# LC_Meter_PTH.net
KiCad netlist of a schematic drawn in EAGLE
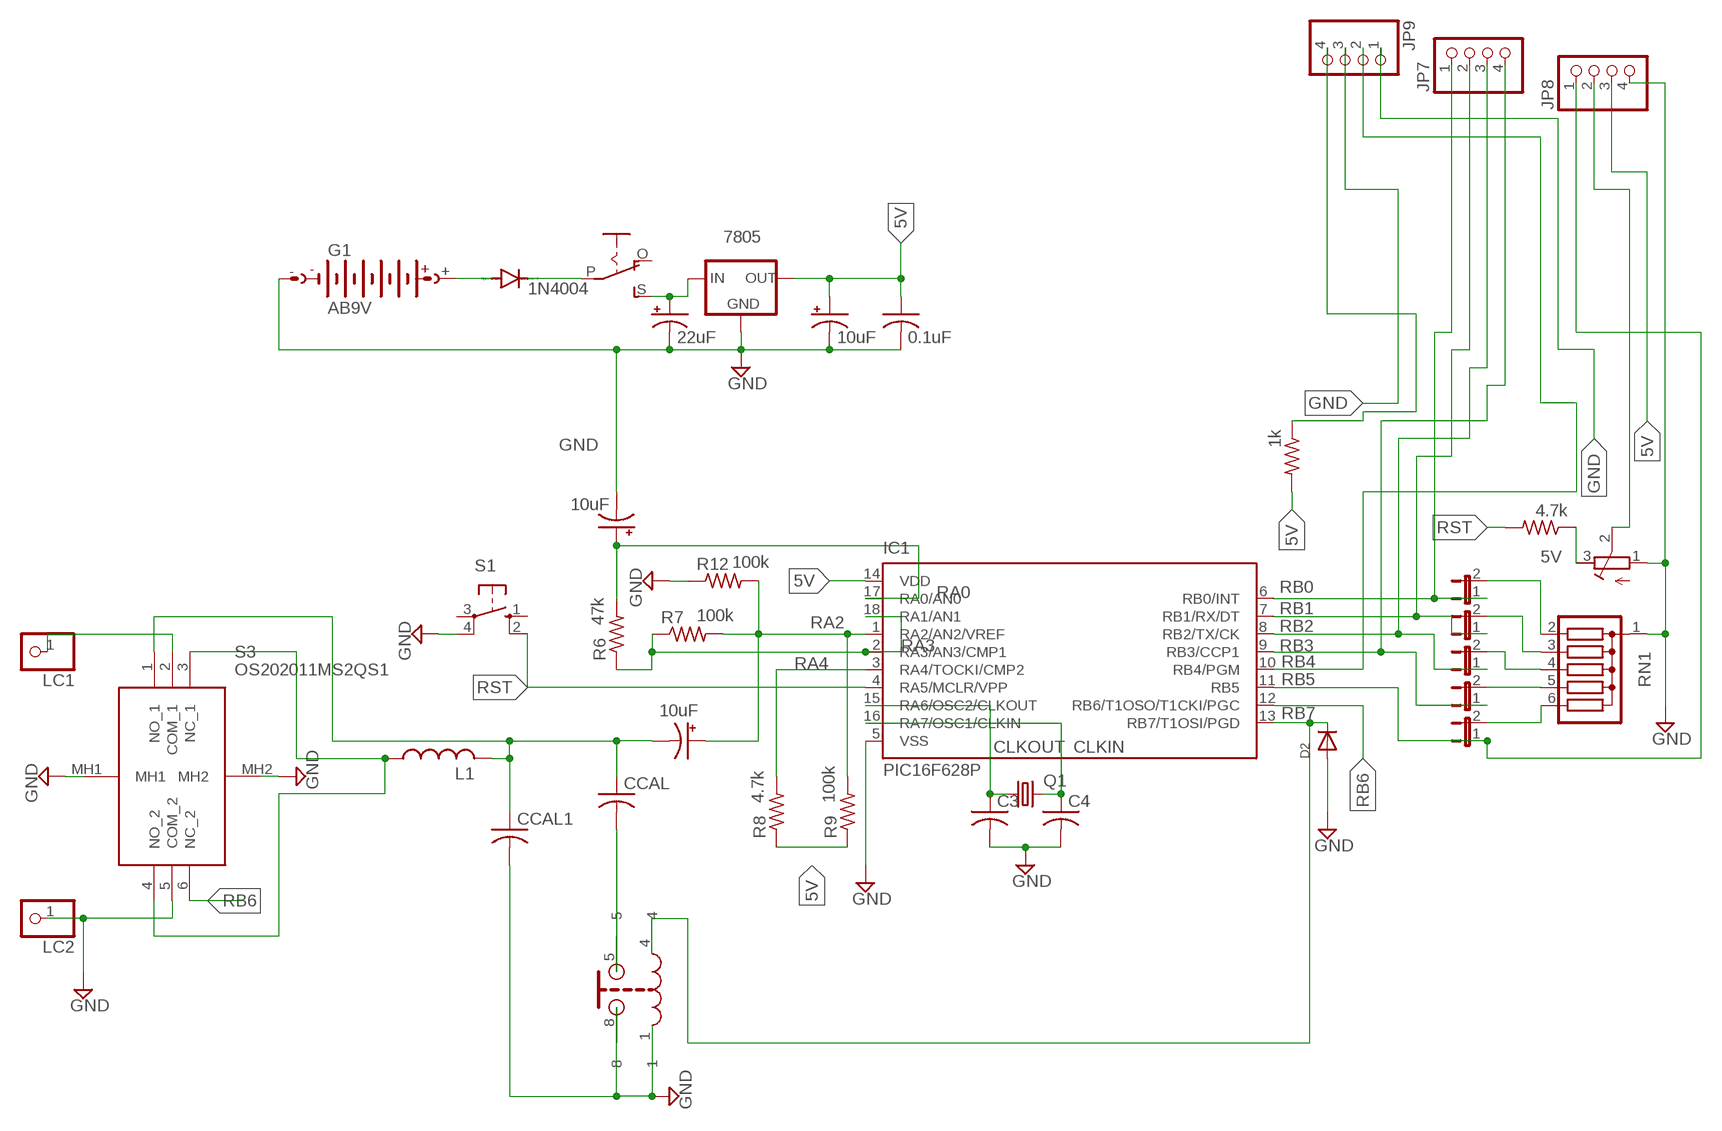
[diagram p0: schematic, sheet 1]

(export (version "E")
  (design (tool "Eeschema 10.0.6"))
  (components
    (comp (ref "C1")
      (value "22uF")
      (footprint "eagle-import:E2,5-7")
      (libsource (lib "eagle-import") (part "CPOL-USE2.5-7"))
    )
    (comp (ref "C2")
      (value "0.1uF")
      (footprint "eagle-import:C050-025X075")
      (libsource (lib "eagle-import") (part "C-US050-025X075"))
    )
    (comp (ref "C3")
      (value "C-US025-030X050")
      (footprint "eagle-import:C025-030X050")
      (libsource (lib "eagle-import") (part "C-US025-030X050"))
    )
    (comp (ref "C4")
      (value "C-US025-030X050")
      (footprint "eagle-import:C025-030X050")
      (libsource (lib "eagle-import") (part "C-US025-030X050"))
    )
    (comp (ref "C5")
      (value "10uF")
      (footprint "eagle-import:E2-4")
      (libsource (lib "eagle-import") (part "rcl_334_CPOL-USE2-4"))
    )
    (comp (ref "C6")
      (value "10uF")
      (footprint "eagle-import:E2-4")
      (libsource (lib "eagle-import") (part "rcl_334_CPOL-USE2-4"))
    )
    (comp (ref "C7")
      (value "10uF")
      (footprint "eagle-import:E2-4")
      (libsource (lib "eagle-import") (part "rcl_334_CPOL-USE2-4"))
    )
    (comp (ref "CCAL")
      (value "C-US050-035X075")
      (footprint "eagle-import:C050-035X075")
      (libsource (lib "eagle-import") (part "C-US050-035X075"))
    )
    (comp (ref "CCAL1")
      (value "C-US050-035X075")
      (footprint "eagle-import:C050-035X075")
      (libsource (lib "eagle-import") (part "C-US050-035X075"))
    )
    (comp (ref "D1")
      (value "1N4004")
      (footprint "eagle-import:DO41-10")
      (libsource (lib "eagle-import") (part "1N4004"))
    )
    (comp (ref "D2")
      (value "DIODEDO-1N4148")
      (footprint "eagle-import:DO-1N4148")
      (libsource (lib "eagle-import") (part "DIODEDO-1N4148"))
    )
    (comp (ref "G1")
      (value "AB9V")
      (footprint "eagle-import:AB9V")
      (libsource (lib "eagle-import") (part "AB9V"))
    )
    (comp (ref "IC1")
      (value "PIC16F628P")
      (footprint "eagle-import:DIL18")
      (fields (field (name "MF") "MICROCHIP") (field (name "MPN") "PIC16F628-04I/P"))
      (libsource (lib "eagle-import") (part "PIC16F62P8"))
    )
    (comp (ref "JP1")
      (value "JP1E")
      (footprint "eagle-import:JP1")
      (libsource (lib "eagle-import") (part "JP1E"))
    )
    (comp (ref "JP2")
      (value "JP1E")
      (footprint "eagle-import:JP1")
      (libsource (lib "eagle-import") (part "JP1E"))
    )
    (comp (ref "JP3")
      (value "JP1E")
      (footprint "eagle-import:JP1")
      (libsource (lib "eagle-import") (part "JP1E"))
    )
    (comp (ref "JP4")
      (value "JP1E")
      (footprint "eagle-import:JP1")
      (libsource (lib "eagle-import") (part "JP1E"))
    )
    (comp (ref "JP5")
      (value "JP1E")
      (footprint "eagle-import:JP1")
      (libsource (lib "eagle-import") (part "JP1E"))
    )
    (comp (ref "JP7")
      (value "PINHD-1X4")
      (footprint "eagle-import:1X04")
      (libsource (lib "eagle-import") (part "PINHD-1X4"))
    )
    (comp (ref "JP8")
      (value "PINHD-1X4")
      (footprint "eagle-import:1X04")
      (libsource (lib "eagle-import") (part "PINHD-1X4"))
    )
    (comp (ref "JP9")
      (value "PINHD-1X4")
      (footprint "eagle-import:1X04")
      (libsource (lib "eagle-import") (part "PINHD-1X4"))
    )
    (comp (ref "L1")
      (value "L-US0207/12")
      (footprint "eagle-import:0207_12")
      (libsource (lib "eagle-import") (part "L-US0207/12"))
    )
    (comp (ref "LC1")
      (value "PINHD-1X1")
      (footprint "eagle-import:1X01")
      (libsource (lib "eagle-import") (part "PINHD-1X1"))
    )
    (comp (ref "LC2")
      (value "PINHD-1X1")
      (footprint "eagle-import:1X01")
      (libsource (lib "eagle-import") (part "PINHD-1X1"))
    )
    (comp (ref "Q1")
      (value "CRYSTALHC49S")
      (footprint "eagle-import:HC49_S")
      (libsource (lib "eagle-import") (part "CRYSTALHC49S"))
    )
    (comp (ref "R1")
      (value "1k")
      (footprint "eagle-import:0207_7")
      (libsource (lib "eagle-import") (part "R-US_0207/7"))
    )
    (comp (ref "R6")
      (value "47k")
      (footprint "eagle-import:0207_7")
      (libsource (lib "eagle-import") (part "R-US_0207/7"))
    )
    (comp (ref "R7")
      (value "100k")
      (footprint "eagle-import:0207_7")
      (libsource (lib "eagle-import") (part "R-US_0207/7"))
    )
    (comp (ref "R8")
      (value "4.7k")
      (footprint "eagle-import:0207_7")
      (libsource (lib "eagle-import") (part "R-US_0207/7"))
    )
    (comp (ref "R9")
      (value "100k")
      (footprint "eagle-import:0207_7")
      (libsource (lib "eagle-import") (part "R-US_0207/7"))
    )
    (comp (ref "R10")
      (value "4.7k")
      (footprint "eagle-import:0207_7")
      (libsource (lib "eagle-import") (part "R-US_0207/7"))
    )
    (comp (ref "R11")
      (value "R-TRIMM3339P")
      (footprint "eagle-import:RTRIM3339P")
      (libsource (lib "eagle-import") (part "R-TRIMM3339P"))
    )
    (comp (ref "R12")
      (value "100k")
      (footprint "eagle-import:0207_7")
      (libsource (lib "eagle-import") (part "R-US_0207/7"))
    )
    (comp (ref "REED")
      (value "REEDRELAY")
      (footprint "eagle-import:COTO2204")
      (libsource (lib "eagle-import") (part "REEDRELAY"))
    )
    (comp (ref "RN1")
      (value "G05R")
      (footprint "eagle-import:SIL6")
      (libsource (lib "eagle-import") (part "G05R"))
    )
    (comp (ref "S1")
      (value "10-XX")
      (footprint "eagle-import:B3F-10XX")
      (fields (field (name "MPN") "B3F-1000"))
      (libsource (lib "eagle-import") (part "10-XX"))
    )
    (comp (ref "S2")
      (value "EG1218S")
      (footprint "eagle-import:EG1218")
      (libsource (lib "eagle-import") (part "EG1218S"))
    )
    (comp (ref "S3")
      (value "OS202011MS2QS1")
      (footprint "eagle-import:OS202011MS2QS1")
      (fields (field (name "MOUSER_PART_NUMBER") "611-OS202011MS2QS1"))
      (libsource (lib "eagle-import") (part "OS202011MS2QS1"))
    )
    (comp (ref "VREG")
      (value "7805")
      (footprint "eagle-import:78XXS")
      (libsource (lib "eagle-import") (part "78XXS"))
    )
  )
  (nets
    (net (code "1") (name "/CLKIN") (class "Default")
      (node (ref "C4") (pin "1") (pinfunction "1_1") (pintype "passive"))
      (node (ref "IC1") (pin "16") (pinfunction "RA7/OSC1/CLKIN_16") (pintype "bidirectional"))
      (node (ref "Q1") (pin "2") (pinfunction "2_2") (pintype "passive"))
    )
    (net (code "2") (name "/CLKOUT") (class "Default")
      (node (ref "C3") (pin "1") (pinfunction "1_1") (pintype "passive"))
      (node (ref "IC1") (pin "15") (pinfunction "RA6/OSC2/CLKOUT_15") (pintype "bidirectional"))
      (node (ref "Q1") (pin "1") (pinfunction "1_1") (pintype "passive"))
    )
    (net (code "3") (name "/RA0") (class "Default")
      (node (ref "C7") (pin "+") (pinfunction "+_+") (pintype "passive"))
      (node (ref "IC1") (pin "17") (pinfunction "RA0/AN0_17") (pintype "bidirectional"))
      (node (ref "R6") (pin "2") (pinfunction "2_2") (pintype "passive"))
    )
    (net (code "4") (name "/RA2") (class "Default")
      (node (ref "C5") (pin "+") (pinfunction "+_+") (pintype "passive"))
      (node (ref "IC1") (pin "1") (pinfunction "RA2/AN2/VREF_1") (pintype "bidirectional"))
      (node (ref "R12") (pin "2") (pinfunction "2_2") (pintype "passive"))
      (node (ref "R7") (pin "2") (pinfunction "2_2") (pintype "passive"))
      (node (ref "R9") (pin "2") (pinfunction "2_2") (pintype "passive"))
    )
    (net (code "5") (name "/RA3") (class "Default")
      (node (ref "IC1") (pin "18") (pinfunction "RA1/AN1_18") (pintype "bidirectional"))
      (node (ref "IC1") (pin "2") (pinfunction "RA3/AN3/CMP1_2") (pintype "bidirectional"))
      (node (ref "R6") (pin "1") (pinfunction "1_1") (pintype "passive"))
      (node (ref "R7") (pin "1") (pinfunction "1_1") (pintype "passive"))
    )
    (net (code "6") (name "/RA4") (class "Default")
      (node (ref "IC1") (pin "3") (pinfunction "RA4/TOCKI/CMP2_3") (pintype "bidirectional"))
      (node (ref "R8") (pin "2") (pinfunction "2_2") (pintype "passive"))
    )
    (net (code "7") (name "/RB0") (class "Default")
      (node (ref "IC1") (pin "6") (pinfunction "RB0/INT_6") (pintype "bidirectional"))
      (node (ref "JP1") (pin "1") (pinfunction "1_1") (pintype "passive"))
      (node (ref "JP7") (pin "1") (pinfunction "1_1") (pintype "passive"))
    )
    (net (code "8") (name "/RB1") (class "Default")
      (node (ref "IC1") (pin "7") (pinfunction "RB1/RX/DT_7") (pintype "bidirectional"))
      (node (ref "JP2") (pin "1") (pinfunction "1_1") (pintype "passive"))
      (node (ref "JP7") (pin "2") (pinfunction "2_2") (pintype "passive"))
    )
    (net (code "9") (name "/RB2") (class "Default")
      (node (ref "IC1") (pin "8") (pinfunction "RB2/TX/CK_8") (pintype "bidirectional"))
      (node (ref "JP3") (pin "1") (pinfunction "1_1") (pintype "passive"))
      (node (ref "JP7") (pin "3") (pinfunction "3_3") (pintype "passive"))
    )
    (net (code "10") (name "/RB3") (class "Default")
      (node (ref "IC1") (pin "9") (pinfunction "RB3/CCP1_9") (pintype "bidirectional"))
      (node (ref "JP4") (pin "1") (pinfunction "1_1") (pintype "passive"))
      (node (ref "JP7") (pin "4") (pinfunction "4_4") (pintype "passive"))
    )
    (net (code "11") (name "/RB4") (class "Default")
      (node (ref "IC1") (pin "10") (pinfunction "RB4/PGM_10") (pintype "bidirectional"))
      (node (ref "JP9") (pin "2") (pinfunction "2_2") (pintype "passive"))
    )
    (net (code "12") (name "/RB5") (class "Default")
      (node (ref "IC1") (pin "11") (pinfunction "RB5_11") (pintype "bidirectional"))
      (node (ref "JP5") (pin "1") (pinfunction "1_1") (pintype "passive"))
      (node (ref "JP8") (pin "1") (pinfunction "1_1") (pintype "passive"))
    )
    (net (code "13") (name "/RB7") (class "Default")
      (node (ref "D2") (pin "C") (pinfunction "C_C") (pintype "passive"))
      (node (ref "IC1") (pin "13") (pinfunction "RB7/T1OSI/PGD_13") (pintype "bidirectional"))
      (node (ref "REED") (pin "4") (pinfunction "4_4") (pintype "bidirectional"))
    )
    (net (code "14") (name "5V") (class "Default")
      (node (ref "C2") (pin "1") (pinfunction "1_1") (pintype "passive"))
      (node (ref "C6") (pin "+") (pinfunction "+_+") (pintype "passive"))
      (node (ref "IC1") (pin "14") (pinfunction "VDD_14") (pintype "power_in"))
      (node (ref "JP8") (pin "3") (pinfunction "3_3") (pintype "passive"))
      (node (ref "R1") (pin "2") (pinfunction "2_2") (pintype "passive"))
      (node (ref "R10") (pin "1") (pinfunction "1_1") (pintype "passive"))
      (node (ref "R11") (pin "3") (pinfunction "E_3") (pintype "passive"))
      (node (ref "R8") (pin "1") (pinfunction "1_1") (pintype "passive"))
      (node (ref "R9") (pin "1") (pinfunction "1_1") (pintype "passive"))
      (node (ref "VREG") (pin "OUT") (pinfunction "OUT_OUT") (pintype "passive"))
    )
    (net (code "15") (name "GND") (class "Default")
      (node (ref "C1") (pin "-") (pinfunction "-_-") (pintype "passive"))
      (node (ref "C2") (pin "2") (pinfunction "2_2") (pintype "passive"))
      (node (ref "C3") (pin "2") (pinfunction "2_2") (pintype "passive"))
      (node (ref "C4") (pin "2") (pinfunction "2_2") (pintype "passive"))
      (node (ref "C6") (pin "-") (pinfunction "-_-") (pintype "passive"))
      (node (ref "C7") (pin "-") (pinfunction "-_-") (pintype "passive"))
      (node (ref "CCAL1") (pin "2") (pinfunction "2_2") (pintype "passive"))
      (node (ref "D2") (pin "A") (pinfunction "A_A") (pintype "passive"))
      (node (ref "G1") (pin "-") (pinfunction "-_-") (pintype "passive"))
      (node (ref "IC1") (pin "5") (pinfunction "VSS_5") (pintype "power_in"))
      (node (ref "JP8") (pin "4") (pinfunction "4_4") (pintype "passive"))
      (node (ref "JP9") (pin "1") (pinfunction "1_1") (pintype "passive"))
      (node (ref "JP9") (pin "3") (pinfunction "3_3") (pintype "passive"))
      (node (ref "LC2") (pin "1") (pinfunction "1_1") (pintype "passive"))
      (node (ref "R11") (pin "1") (pinfunction "A_1") (pintype "passive"))
      (node (ref "R12") (pin "1") (pinfunction "1_1") (pintype "passive"))
      (node (ref "REED") (pin "1") (pinfunction "1_1") (pintype "bidirectional"))
      (node (ref "REED") (pin "8") (pinfunction "8_8") (pintype "bidirectional"))
      (node (ref "RN1") (pin "1") (pinfunction "1_1") (pintype "passive"))
      (node (ref "S1") (pin "4") (pinfunction "P1_4") (pintype "passive"))
      (node (ref "S3") (pin "5") (pinfunction "COM_2_5") (pintype "bidirectional"))
      (node (ref "S3") (pin "MH1") (pinfunction "MH1_MH1") (pintype "bidirectional"))
      (node (ref "S3") (pin "MH2") (pinfunction "MH2_MH2") (pintype "bidirectional"))
      (node (ref "VREG") (pin "GND") (pinfunction "GND_GND") (pintype "input"))
    )
    (net (code "16") (name "Net-(C1-Pad+)") (class "Default")
      (node (ref "C1") (pin "+") (pinfunction "+_+") (pintype "passive"))
      (node (ref "S2") (pin "S") (pinfunction "S_S") (pintype "passive"))
      (node (ref "VREG") (pin "IN") (pinfunction "IN_IN") (pintype "input"))
    )
    (net (code "17") (name "Net-(CCAL-Pad2)") (class "Default")
      (node (ref "CCAL") (pin "2") (pinfunction "2_2") (pintype "passive"))
      (node (ref "REED") (pin "5") (pinfunction "5_5") (pintype "bidirectional"))
    )
    (net (code "18") (name "Net-(D1-PadA)") (class "Default")
      (node (ref "D1") (pin "A") (pinfunction "A_A") (pintype "passive"))
      (node (ref "G1") (pin "+") (pinfunction "+_+") (pintype "passive"))
    )
    (net (code "19") (name "Net-(D1-PadC)") (class "Default")
      (node (ref "D1") (pin "C") (pinfunction "C_C") (pintype "passive"))
      (node (ref "S2") (pin "P") (pinfunction "P_P") (pintype "passive"))
    )
    (net (code "20") (name "Net-(JP1-Pad2)") (class "Default")
      (node (ref "JP1") (pin "2") (pinfunction "2_2") (pintype "passive"))
      (node (ref "RN1") (pin "2") (pinfunction "2_2") (pintype "passive"))
    )
    (net (code "21") (name "Net-(JP2-Pad2)") (class "Default")
      (node (ref "JP2") (pin "2") (pinfunction "2_2") (pintype "passive"))
      (node (ref "RN1") (pin "3") (pinfunction "3_3") (pintype "passive"))
    )
    (net (code "22") (name "Net-(JP3-Pad2)") (class "Default")
      (node (ref "JP3") (pin "2") (pinfunction "2_2") (pintype "passive"))
      (node (ref "RN1") (pin "4") (pinfunction "4_4") (pintype "passive"))
    )
    (net (code "23") (name "Net-(JP4-Pad2)") (class "Default")
      (node (ref "JP4") (pin "2") (pinfunction "2_2") (pintype "passive"))
      (node (ref "RN1") (pin "5") (pinfunction "5_5") (pintype "passive"))
    )
    (net (code "24") (name "Net-(JP5-Pad2)") (class "Default")
      (node (ref "JP5") (pin "2") (pinfunction "2_2") (pintype "passive"))
      (node (ref "RN1") (pin "6") (pinfunction "6_6") (pintype "passive"))
    )
    (net (code "25") (name "Net-(JP9-Pad4)") (class "Default")
      (node (ref "JP9") (pin "4") (pinfunction "4_4") (pintype "passive"))
      (node (ref "R1") (pin "1") (pinfunction "1_1") (pintype "passive"))
    )
    (net (code "26") (name "Net-(R11-S)") (class "Default")
      (node (ref "JP8") (pin "2") (pinfunction "2_2") (pintype "passive"))
      (node (ref "R11") (pin "2") (pinfunction "S_2") (pintype "passive"))
    )
    (net (code "27") (name "Net-(S3-COM_1)") (class "Default")
      (node (ref "LC1") (pin "1") (pinfunction "1_1") (pintype "passive"))
      (node (ref "S3") (pin "2") (pinfunction "COM_1_2") (pintype "bidirectional"))
    )
    (net (code "28") (name "Net-(S3-NC_1)") (class "Default")
      (node (ref "L1") (pin "1") (pinfunction "1_1") (pintype "passive"))
      (node (ref "S3") (pin "3") (pinfunction "NC_1_3") (pintype "bidirectional"))
      (node (ref "S3") (pin "4") (pinfunction "NO_2_4") (pintype "bidirectional"))
    )
    (net (code "29") (name "Net-(S3-NO_1)") (class "Default")
      (node (ref "C5") (pin "-") (pinfunction "-_-") (pintype "passive"))
      (node (ref "CCAL") (pin "1") (pinfunction "1_1") (pintype "passive"))
      (node (ref "CCAL1") (pin "1") (pinfunction "1_1") (pintype "passive"))
      (node (ref "L1") (pin "2") (pinfunction "2_2") (pintype "passive"))
      (node (ref "S3") (pin "1") (pinfunction "NO_1_1") (pintype "bidirectional"))
    )
    (net (code "30") (name "RB6") (class "Default")
      (node (ref "IC1") (pin "12") (pinfunction "RB6/T1OSO/T1CKI/PGC_12") (pintype "bidirectional"))
      (node (ref "S3") (pin "6") (pinfunction "NC_2_6") (pintype "bidirectional"))
    )
    (net (code "31") (name "RST") (class "Default")
      (node (ref "IC1") (pin "4") (pinfunction "RA5/MCLR/VPP_4") (pintype "bidirectional"))
      (node (ref "R10") (pin "2") (pinfunction "2_2") (pintype "passive"))
      (node (ref "S1") (pin "2") (pinfunction "S1_2") (pintype "passive"))
    )
    (net (code "32") (name "unconnected-(S1-P-Pad3)") (class "Default")
      (node (ref "S1") (pin "3") (pinfunction "P_3") (pintype "passive"))
    )
    (net (code "33") (name "unconnected-(S1-S-Pad1)") (class "Default")
      (node (ref "S1") (pin "1") (pinfunction "S_1") (pintype "passive"))
    )
    (net (code "34") (name "unconnected-(S2-PadO)") (class "Default")
      (node (ref "S2") (pin "O") (pinfunction "O_O") (pintype "passive"))
    )
  )
)
